# CharlieplexedPairReactorBreakout.net
KiCad netlist of a schematic drawn in EAGLE
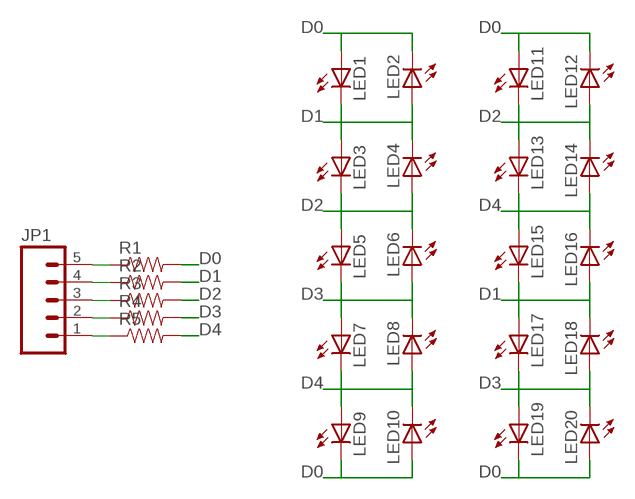
[diagram p0: schematic, sheet 1]

(export (version "E")
  (design (tool "Eeschema 10.0.6"))
  (components
    (comp (ref "JP1")
      (value "M05PTH")
      (footprint "eagle-import:1X05")
      (libsource (lib "eagle-import") (part "M05PTH"))
    )
    (comp (ref "LED1")
      (value "LEDOVAL")
      (footprint "eagle-import:LED-OVAL")
      (libsource (lib "eagle-import") (part "LEDOVAL"))
    )
    (comp (ref "LED2")
      (value "LEDOVAL")
      (footprint "eagle-import:LED-OVAL")
      (libsource (lib "eagle-import") (part "LEDOVAL"))
    )
    (comp (ref "LED3")
      (value "LEDOVAL")
      (footprint "eagle-import:LED-OVAL")
      (libsource (lib "eagle-import") (part "LEDOVAL"))
    )
    (comp (ref "LED4")
      (value "LEDOVAL")
      (footprint "eagle-import:LED-OVAL")
      (libsource (lib "eagle-import") (part "LEDOVAL"))
    )
    (comp (ref "LED5")
      (value "LEDOVAL")
      (footprint "eagle-import:LED-OVAL")
      (libsource (lib "eagle-import") (part "LEDOVAL"))
    )
    (comp (ref "LED6")
      (value "LEDOVAL")
      (footprint "eagle-import:LED-OVAL")
      (libsource (lib "eagle-import") (part "LEDOVAL"))
    )
    (comp (ref "LED7")
      (value "LEDOVAL")
      (footprint "eagle-import:LED-OVAL")
      (libsource (lib "eagle-import") (part "LEDOVAL"))
    )
    (comp (ref "LED8")
      (value "LEDOVAL")
      (footprint "eagle-import:LED-OVAL")
      (libsource (lib "eagle-import") (part "LEDOVAL"))
    )
    (comp (ref "LED9")
      (value "LEDOVAL")
      (footprint "eagle-import:LED-OVAL")
      (libsource (lib "eagle-import") (part "LEDOVAL"))
    )
    (comp (ref "LED10")
      (value "LEDOVAL")
      (footprint "eagle-import:LED-OVAL")
      (libsource (lib "eagle-import") (part "LEDOVAL"))
    )
    (comp (ref "LED11")
      (value "LEDOVAL")
      (footprint "eagle-import:LED-OVAL")
      (libsource (lib "eagle-import") (part "LEDOVAL"))
    )
    (comp (ref "LED12")
      (value "LEDOVAL")
      (footprint "eagle-import:LED-OVAL")
      (libsource (lib "eagle-import") (part "LEDOVAL"))
    )
    (comp (ref "LED13")
      (value "LEDOVAL")
      (footprint "eagle-import:LED-OVAL")
      (libsource (lib "eagle-import") (part "LEDOVAL"))
    )
    (comp (ref "LED14")
      (value "LEDOVAL")
      (footprint "eagle-import:LED-OVAL")
      (libsource (lib "eagle-import") (part "LEDOVAL"))
    )
    (comp (ref "LED15")
      (value "LEDOVAL")
      (footprint "eagle-import:LED-OVAL")
      (libsource (lib "eagle-import") (part "LEDOVAL"))
    )
    (comp (ref "LED16")
      (value "LEDOVAL")
      (footprint "eagle-import:LED-OVAL")
      (libsource (lib "eagle-import") (part "LEDOVAL"))
    )
    (comp (ref "LED17")
      (value "LEDOVAL")
      (footprint "eagle-import:LED-OVAL")
      (libsource (lib "eagle-import") (part "LEDOVAL"))
    )
    (comp (ref "LED18")
      (value "LEDOVAL")
      (footprint "eagle-import:LED-OVAL")
      (libsource (lib "eagle-import") (part "LEDOVAL"))
    )
    (comp (ref "LED19")
      (value "LEDOVAL")
      (footprint "eagle-import:LED-OVAL")
      (libsource (lib "eagle-import") (part "LEDOVAL"))
    )
    (comp (ref "LED20")
      (value "LEDOVAL")
      (footprint "eagle-import:LED-OVAL")
      (libsource (lib "eagle-import") (part "LEDOVAL"))
    )
    (comp (ref "R1")
      (value "RESISTORAXIAL-0.3")
      (footprint "eagle-import:AXIAL-0.3")
      (libsource (lib "eagle-import") (part "RESISTORAXIAL-0.3"))
    )
    (comp (ref "R2")
      (value "RESISTORAXIAL-0.3")
      (footprint "eagle-import:AXIAL-0.3")
      (libsource (lib "eagle-import") (part "RESISTORAXIAL-0.3"))
    )
    (comp (ref "R3")
      (value "RESISTORAXIAL-0.3")
      (footprint "eagle-import:AXIAL-0.3")
      (libsource (lib "eagle-import") (part "RESISTORAXIAL-0.3"))
    )
    (comp (ref "R4")
      (value "RESISTORAXIAL-0.3")
      (footprint "eagle-import:AXIAL-0.3")
      (libsource (lib "eagle-import") (part "RESISTORAXIAL-0.3"))
    )
    (comp (ref "R5")
      (value "RESISTORAXIAL-0.3")
      (footprint "eagle-import:AXIAL-0.3")
      (libsource (lib "eagle-import") (part "RESISTORAXIAL-0.3"))
    )
  )
  (nets
    (net (code "1") (name "/D0") (class "Default")
      (node (ref "LED1") (pin "ANODE") (pinfunction "A_ANODE") (pintype "passive"))
      (node (ref "LED10") (pin "ANODE") (pinfunction "A_ANODE") (pintype "passive"))
      (node (ref "LED11") (pin "ANODE") (pinfunction "A_ANODE") (pintype "passive"))
      (node (ref "LED12") (pin "CATHODE") (pinfunction "C_CATHODE") (pintype "passive"))
      (node (ref "LED19") (pin "CATHODE") (pinfunction "C_CATHODE") (pintype "passive"))
      (node (ref "LED2") (pin "CATHODE") (pinfunction "C_CATHODE") (pintype "passive"))
      (node (ref "LED20") (pin "ANODE") (pinfunction "A_ANODE") (pintype "passive"))
      (node (ref "LED9") (pin "CATHODE") (pinfunction "C_CATHODE") (pintype "passive"))
      (node (ref "R1") (pin "P$2") (pinfunction "2_P$2") (pintype "passive"))
    )
    (net (code "2") (name "/D1") (class "Default")
      (node (ref "LED1") (pin "CATHODE") (pinfunction "C_CATHODE") (pintype "passive"))
      (node (ref "LED15") (pin "CATHODE") (pinfunction "C_CATHODE") (pintype "passive"))
      (node (ref "LED16") (pin "ANODE") (pinfunction "A_ANODE") (pintype "passive"))
      (node (ref "LED17") (pin "ANODE") (pinfunction "A_ANODE") (pintype "passive"))
      (node (ref "LED18") (pin "CATHODE") (pinfunction "C_CATHODE") (pintype "passive"))
      (node (ref "LED2") (pin "ANODE") (pinfunction "A_ANODE") (pintype "passive"))
      (node (ref "LED3") (pin "ANODE") (pinfunction "A_ANODE") (pintype "passive"))
      (node (ref "LED4") (pin "CATHODE") (pinfunction "C_CATHODE") (pintype "passive"))
      (node (ref "R2") (pin "P$2") (pinfunction "2_P$2") (pintype "passive"))
    )
    (net (code "3") (name "/D2") (class "Default")
      (node (ref "LED11") (pin "CATHODE") (pinfunction "C_CATHODE") (pintype "passive"))
      (node (ref "LED12") (pin "ANODE") (pinfunction "A_ANODE") (pintype "passive"))
      (node (ref "LED13") (pin "ANODE") (pinfunction "A_ANODE") (pintype "passive"))
      (node (ref "LED14") (pin "CATHODE") (pinfunction "C_CATHODE") (pintype "passive"))
      (node (ref "LED3") (pin "CATHODE") (pinfunction "C_CATHODE") (pintype "passive"))
      (node (ref "LED4") (pin "ANODE") (pinfunction "A_ANODE") (pintype "passive"))
      (node (ref "LED5") (pin "ANODE") (pinfunction "A_ANODE") (pintype "passive"))
      (node (ref "LED6") (pin "CATHODE") (pinfunction "C_CATHODE") (pintype "passive"))
      (node (ref "R3") (pin "P$2") (pinfunction "2_P$2") (pintype "passive"))
    )
    (net (code "4") (name "/D3") (class "Default")
      (node (ref "LED17") (pin "CATHODE") (pinfunction "C_CATHODE") (pintype "passive"))
      (node (ref "LED18") (pin "ANODE") (pinfunction "A_ANODE") (pintype "passive"))
      (node (ref "LED19") (pin "ANODE") (pinfunction "A_ANODE") (pintype "passive"))
      (node (ref "LED20") (pin "CATHODE") (pinfunction "C_CATHODE") (pintype "passive"))
      (node (ref "LED5") (pin "CATHODE") (pinfunction "C_CATHODE") (pintype "passive"))
      (node (ref "LED6") (pin "ANODE") (pinfunction "A_ANODE") (pintype "passive"))
      (node (ref "LED7") (pin "ANODE") (pinfunction "A_ANODE") (pintype "passive"))
      (node (ref "LED8") (pin "CATHODE") (pinfunction "C_CATHODE") (pintype "passive"))
      (node (ref "R4") (pin "P$2") (pinfunction "2_P$2") (pintype "passive"))
    )
    (net (code "5") (name "/D4") (class "Default")
      (node (ref "LED10") (pin "CATHODE") (pinfunction "C_CATHODE") (pintype "passive"))
      (node (ref "LED13") (pin "CATHODE") (pinfunction "C_CATHODE") (pintype "passive"))
      (node (ref "LED14") (pin "ANODE") (pinfunction "A_ANODE") (pintype "passive"))
      (node (ref "LED15") (pin "ANODE") (pinfunction "A_ANODE") (pintype "passive"))
      (node (ref "LED16") (pin "CATHODE") (pinfunction "C_CATHODE") (pintype "passive"))
      (node (ref "LED7") (pin "CATHODE") (pinfunction "C_CATHODE") (pintype "passive"))
      (node (ref "LED8") (pin "ANODE") (pinfunction "A_ANODE") (pintype "passive"))
      (node (ref "LED9") (pin "ANODE") (pinfunction "A_ANODE") (pintype "passive"))
      (node (ref "R5") (pin "P$2") (pinfunction "2_P$2") (pintype "passive"))
    )
    (net (code "6") (name "Net-(R1-1)") (class "Default")
      (node (ref "JP1") (pin "5") (pinfunction "5_5") (pintype "passive"))
      (node (ref "R1") (pin "P$1") (pinfunction "1_P$1") (pintype "passive"))
    )
    (net (code "7") (name "Net-(R2-1)") (class "Default")
      (node (ref "JP1") (pin "4") (pinfunction "4_4") (pintype "passive"))
      (node (ref "R2") (pin "P$1") (pinfunction "1_P$1") (pintype "passive"))
    )
    (net (code "8") (name "Net-(R3-1)") (class "Default")
      (node (ref "JP1") (pin "3") (pinfunction "3_3") (pintype "passive"))
      (node (ref "R3") (pin "P$1") (pinfunction "1_P$1") (pintype "passive"))
    )
    (net (code "9") (name "Net-(R4-1)") (class "Default")
      (node (ref "JP1") (pin "2") (pinfunction "2_2") (pintype "passive"))
      (node (ref "R4") (pin "P$1") (pinfunction "1_P$1") (pintype "passive"))
    )
    (net (code "10") (name "Net-(R5-1)") (class "Default")
      (node (ref "JP1") (pin "1") (pinfunction "1_1") (pintype "passive"))
      (node (ref "R5") (pin "P$1") (pinfunction "1_P$1") (pintype "passive"))
    )
  )
)
